# led_driver_3A_flat.net
KiCad netlist of a schematic drawn in EAGLE
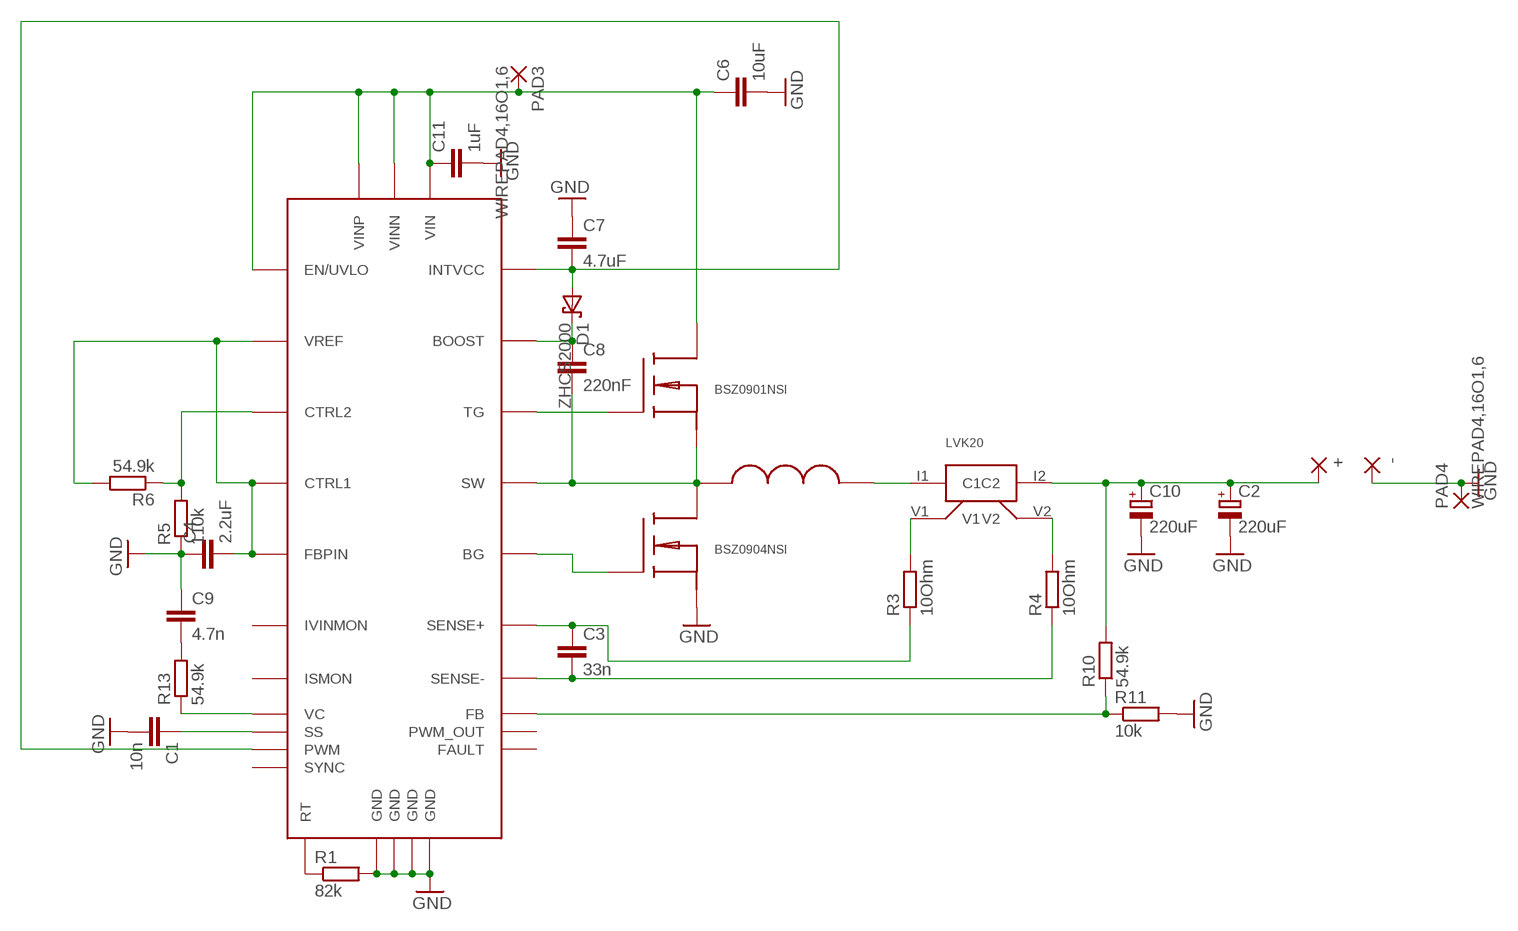
[diagram p0: schematic, sheet 1]

(export (version "E")
  (design (tool "Eeschema 10.0.6"))
  (components
    (comp (ref "+")
      (value "2,15/1,0")
      (footprint "eagle-import:2,15_1,0")
      (libsource (lib "eagle-import") (part "2,15/1,0"))
    )
    (comp (ref "-")
      (value "2,15/1,0")
      (footprint "eagle-import:2,15_1,0")
      (libsource (lib "eagle-import") (part "2,15/1,0"))
    )
    (comp (ref "C1")
      (value "10n")
      (footprint "eagle-import:C0402")
      (libsource (lib "eagle-import") (part "C-EUC0402"))
    )
    (comp (ref "C2")
      (value "220uF")
      (footprint "eagle-import:SMC_D")
      (libsource (lib "eagle-import") (part "CPOL-EUSMCD"))
    )
    (comp (ref "C3")
      (value "33n")
      (footprint "eagle-import:C0402")
      (libsource (lib "eagle-import") (part "C-EUC0402"))
    )
    (comp (ref "C4")
      (value "2.2uF")
      (footprint "eagle-import:C0805")
      (libsource (lib "eagle-import") (part "C-EUC0805"))
    )
    (comp (ref "C6")
      (value "10uF")
      (footprint "eagle-import:C2220K")
      (libsource (lib "eagle-import") (part "C-EUC2220K"))
    )
    (comp (ref "C7")
      (value "4.7uF")
      (footprint "eagle-import:C1206")
      (libsource (lib "eagle-import") (part "C-EUC1206"))
    )
    (comp (ref "C8")
      (value "220nF")
      (footprint "eagle-import:C0603")
      (libsource (lib "eagle-import") (part "C-EUC0603"))
    )
    (comp (ref "C9")
      (value "4.7n")
      (footprint "eagle-import:C0402")
      (libsource (lib "eagle-import") (part "C-EUC0402"))
    )
    (comp (ref "C10")
      (value "220uF")
      (footprint "eagle-import:SMC_D")
      (libsource (lib "eagle-import") (part "CPOL-EUSMCD"))
    )
    (comp (ref "C11")
      (value "1uF")
      (footprint "eagle-import:C1206")
      (libsource (lib "eagle-import") (part "C-EUC1206"))
    )
    (comp (ref "D1")
      (value "ZHCS2000")
      (footprint "eagle-import:SOT23-6")
      (libsource (lib "eagle-import") (part "ZHCS2000"))
    )
    (comp (ref "PAD3")
      (value "WIREPAD4,16O1,6")
      (footprint "eagle-import:4,16O1,6")
      (libsource (lib "eagle-import") (part "WIREPAD4,16O1,6"))
    )
    (comp (ref "PAD4")
      (value "WIREPAD4,16O1,6")
      (footprint "eagle-import:4,16O1,6")
      (libsource (lib "eagle-import") (part "WIREPAD4,16O1,6"))
    )
    (comp (ref "R1")
      (value "82k")
      (footprint "eagle-import:R0402")
      (libsource (lib "eagle-import") (part "R-EU_R0402"))
    )
    (comp (ref "R3")
      (value "10Ohm")
      (footprint "eagle-import:R0402")
      (libsource (lib "eagle-import") (part "R-EU_R0402"))
    )
    (comp (ref "R4")
      (value "10Ohm")
      (footprint "eagle-import:R0402")
      (libsource (lib "eagle-import") (part "R-EU_R0402"))
    )
    (comp (ref "R5")
      (value "110k")
      (footprint "eagle-import:R0402")
      (libsource (lib "eagle-import") (part "R-EU_R0402"))
    )
    (comp (ref "R6")
      (value "54.9k")
      (footprint "eagle-import:R0402")
      (libsource (lib "eagle-import") (part "R-EU_R0402"))
    )
    (comp (ref "R10")
      (value "54.9k")
      (footprint "eagle-import:R0402")
      (libsource (lib "eagle-import") (part "R-EU_R0402"))
    )
    (comp (ref "R11")
      (value "10k")
      (footprint "eagle-import:R0402")
      (libsource (lib "eagle-import") (part "R-EU_R0402"))
    )
    (comp (ref "R13")
      (value "54.9k")
      (footprint "eagle-import:R0402")
      (libsource (lib "eagle-import") (part "R-EU_R0402"))
    )
    (comp (ref "U$1")
      (value "LT3763")
      (footprint "eagle-import:TSSOP-28")
      (libsource (lib "eagle-import") (part "LT3763"))
    )
    (comp (ref "U$2")
      (value "PG0077")
      (footprint "eagle-import:PG0077")
      (libsource (lib "eagle-import") (part "PG0077"))
    )
    (comp (ref "U$3")
      (value "BSZ0901NSI")
      (footprint "eagle-import:BSZ090X")
      (libsource (lib "eagle-import") (part "BSZ090X"))
    )
    (comp (ref "U$4")
      (value "BSZ0904NSI")
      (footprint "eagle-import:BSZ090X")
      (libsource (lib "eagle-import") (part "BSZ090X"))
    )
    (comp (ref "U$5")
      (value "LVK20")
      (footprint "eagle-import:LVK20")
      (libsource (lib "eagle-import") (part "LVK20"))
    )
  )
  (nets
    (net (code "1") (name "GND") (class "Default")
      (node (ref "-") (pin "1") (pinfunction "P_1") (pintype "passive"))
      (node (ref "C1") (pin "2") (pinfunction "2_2") (pintype "passive"))
      (node (ref "C10") (pin "-") (pinfunction "-_-") (pintype "passive"))
      (node (ref "C11") (pin "2") (pinfunction "2_2") (pintype "passive"))
      (node (ref "C2") (pin "-") (pinfunction "-_-") (pintype "passive"))
      (node (ref "C4") (pin "1") (pinfunction "1_1") (pintype "passive"))
      (node (ref "C6") (pin "2") (pinfunction "2_2") (pintype "passive"))
      (node (ref "C7") (pin "1") (pinfunction "1_1") (pintype "passive"))
      (node (ref "C9") (pin "1") (pinfunction "1_1") (pintype "passive"))
      (node (ref "PAD4") (pin "1") (pinfunction "P_1") (pintype "passive"))
      (node (ref "R1") (pin "2") (pinfunction "2_2") (pintype "passive"))
      (node (ref "R11") (pin "2") (pinfunction "2_2") (pintype "passive"))
      (node (ref "R5") (pin "1") (pinfunction "1_1") (pintype "passive"))
      (node (ref "U$1") (pin "P$12") (pinfunction "GND_P$12") (pintype "bidirectional"))
      (node (ref "U$1") (pin "P$23") (pinfunction "GND_P$23") (pintype "bidirectional"))
      (node (ref "U$1") (pin "P$28") (pinfunction "GND_P$28") (pintype "bidirectional"))
      (node (ref "U$1") (pin "TH") (pinfunction "GND_TH") (pintype "bidirectional"))
      (node (ref "U$4") (pin "S@1") (pinfunction "S_S@1") (pintype "bidirectional"))
      (node (ref "U$4") (pin "S@2") (pinfunction "S_S@2") (pintype "bidirectional"))
      (node (ref "U$4") (pin "S@3") (pinfunction "S_S@3") (pintype "bidirectional"))
      (node (ref "U$4") (pin "S@4") (pinfunction "S_S@4") (pintype "bidirectional"))
    )
    (net (code "2") (name "Net-(+-P)") (class "Default")
      (node (ref "+") (pin "1") (pinfunction "P_1") (pintype "passive"))
      (node (ref "C10") (pin "+") (pinfunction "+_+") (pintype "passive"))
      (node (ref "C2") (pin "+") (pinfunction "+_+") (pintype "passive"))
      (node (ref "R10") (pin "2") (pinfunction "2_2") (pintype "passive"))
      (node (ref "U$5") (pin "I2") (pinfunction "C2_I2") (pintype "bidirectional"))
    )
    (net (code "3") (name "Net-(C9-Pad2)") (class "Default")
      (node (ref "C9") (pin "2") (pinfunction "2_2") (pintype "passive"))
      (node (ref "R13") (pin "2") (pinfunction "2_2") (pintype "passive"))
    )
    (net (code "4") (name "Net-(PAD3-P)") (class "Default")
      (node (ref "C11") (pin "1") (pinfunction "1_1") (pintype "passive"))
      (node (ref "C6") (pin "1") (pinfunction "1_1") (pintype "passive"))
      (node (ref "PAD3") (pin "1") (pinfunction "P_1") (pintype "passive"))
      (node (ref "U$1") (pin "P$3") (pinfunction "VIN_P$3") (pintype "bidirectional"))
      (node (ref "U$1") (pin "P$4") (pinfunction "EN/UVLO_P$4") (pintype "bidirectional"))
      (node (ref "U$1") (pin "P$6") (pinfunction "VINN_P$6") (pintype "bidirectional"))
      (node (ref "U$1") (pin "P$7") (pinfunction "VINP_P$7") (pintype "bidirectional"))
      (node (ref "U$3") (pin "D") (pinfunction "D_D") (pintype "bidirectional"))
      (node (ref "U$3") (pin "D@1") (pinfunction "D_D@1") (pintype "bidirectional"))
      (node (ref "U$3") (pin "D@2") (pinfunction "D_D@2") (pintype "bidirectional"))
      (node (ref "U$3") (pin "D@3") (pinfunction "D_D@3") (pintype "bidirectional"))
      (node (ref "U$3") (pin "D@4") (pinfunction "D_D@4") (pintype "bidirectional"))
    )
    (net (code "5") (name "Net-(R3-Pad2)") (class "Default")
      (node (ref "R3") (pin "2") (pinfunction "2_2") (pintype "passive"))
      (node (ref "U$5") (pin "V1") (pinfunction "V1_V1") (pintype "bidirectional"))
    )
    (net (code "6") (name "Net-(R4-Pad2)") (class "Default")
      (node (ref "R4") (pin "2") (pinfunction "2_2") (pintype "passive"))
      (node (ref "U$5") (pin "V2") (pinfunction "V2_V2") (pintype "bidirectional"))
    )
    (net (code "7") (name "Net-(U$1-BG)") (class "Default")
      (node (ref "U$1") (pin "P$1") (pinfunction "BG_P$1") (pintype "bidirectional"))
      (node (ref "U$4") (pin "G") (pinfunction "G_G") (pintype "bidirectional"))
    )
    (net (code "8") (name "Net-(U$1-BOOST)") (class "Default")
      (node (ref "C8") (pin "1") (pinfunction "1_1") (pintype "passive"))
      (node (ref "D1") (pin "1") (pinfunction "K_1") (pintype "passive"))
      (node (ref "D1") (pin "2") (pinfunction "K_2") (pintype "passive"))
      (node (ref "D1") (pin "5") (pinfunction "K_5") (pintype "passive"))
      (node (ref "D1") (pin "6") (pinfunction "K_6") (pintype "passive"))
      (node (ref "U$1") (pin "P$27") (pinfunction "BOOST_P$27") (pintype "bidirectional"))
    )
    (net (code "9") (name "Net-(U$1-CTRL1)") (class "Default")
      (node (ref "C4") (pin "2") (pinfunction "2_2") (pintype "passive"))
      (node (ref "R6") (pin "2") (pinfunction "2_2") (pintype "passive"))
      (node (ref "U$1") (pin "P$10") (pinfunction "FBPIN_P$10") (pintype "bidirectional"))
      (node (ref "U$1") (pin "P$14") (pinfunction "CTRL1_P$14") (pintype "bidirectional"))
      (node (ref "U$1") (pin "P$5") (pinfunction "VREF_P$5") (pintype "bidirectional"))
    )
    (net (code "10") (name "Net-(U$1-CTRL2)") (class "Default")
      (node (ref "R5") (pin "2") (pinfunction "2_2") (pintype "passive"))
      (node (ref "R6") (pin "1") (pinfunction "1_1") (pintype "passive"))
      (node (ref "U$1") (pin "P$13") (pinfunction "CTRL2_P$13") (pintype "bidirectional"))
    )
    (net (code "11") (name "Net-(U$1-FB)") (class "Default")
      (node (ref "R10") (pin "1") (pinfunction "1_1") (pintype "passive"))
      (node (ref "R11") (pin "1") (pinfunction "1_1") (pintype "passive"))
      (node (ref "U$1") (pin "P$11") (pinfunction "FB_P$11") (pintype "bidirectional"))
    )
    (net (code "12") (name "Net-(U$1-INTVCC)") (class "Default")
      (node (ref "C7") (pin "2") (pinfunction "2_2") (pintype "passive"))
      (node (ref "D1") (pin "3") (pinfunction "A_3") (pintype "passive"))
      (node (ref "D1") (pin "4") (pinfunction "A_4") (pintype "passive"))
      (node (ref "U$1") (pin "P$2") (pinfunction "INTVCC_P$2") (pintype "bidirectional"))
      (node (ref "U$1") (pin "P$22") (pinfunction "PWM_P$22") (pintype "bidirectional"))
    )
    (net (code "13") (name "Net-(U$1-RT)") (class "Default")
      (node (ref "R1") (pin "1") (pinfunction "1_1") (pintype "passive"))
      (node (ref "U$1") (pin "P$20") (pinfunction "RT_P$20") (pintype "bidirectional"))
    )
    (net (code "14") (name "Net-(U$1-SENSE+)") (class "Default")
      (node (ref "C3") (pin "1") (pinfunction "1_1") (pintype "passive"))
      (node (ref "R3") (pin "1") (pinfunction "1_1") (pintype "passive"))
      (node (ref "U$1") (pin "P$17") (pinfunction "SENSE+_P$17") (pintype "bidirectional"))
    )
    (net (code "15") (name "Net-(U$1-SENSE-)") (class "Default")
      (node (ref "C3") (pin "2") (pinfunction "2_2") (pintype "passive"))
      (node (ref "R4") (pin "1") (pinfunction "1_1") (pintype "passive"))
      (node (ref "U$1") (pin "P$16") (pinfunction "SENSE-_P$16") (pintype "bidirectional"))
    )
    (net (code "16") (name "Net-(U$1-SS)") (class "Default")
      (node (ref "C1") (pin "1") (pinfunction "1_1") (pintype "passive"))
      (node (ref "U$1") (pin "P$15") (pinfunction "SS_P$15") (pintype "bidirectional"))
    )
    (net (code "17") (name "Net-(U$1-SW)") (class "Default")
      (node (ref "C8") (pin "2") (pinfunction "2_2") (pintype "passive"))
      (node (ref "U$1") (pin "P$26") (pinfunction "SW_P$26") (pintype "bidirectional"))
      (node (ref "U$2") (pin "P$1") (pinfunction "P$1_P$1") (pintype "bidirectional"))
      (node (ref "U$3") (pin "S@1") (pinfunction "S_S@1") (pintype "bidirectional"))
      (node (ref "U$3") (pin "S@2") (pinfunction "S_S@2") (pintype "bidirectional"))
      (node (ref "U$3") (pin "S@3") (pinfunction "S_S@3") (pintype "bidirectional"))
      (node (ref "U$3") (pin "S@4") (pinfunction "S_S@4") (pintype "bidirectional"))
      (node (ref "U$4") (pin "D") (pinfunction "D_D") (pintype "bidirectional"))
      (node (ref "U$4") (pin "D@1") (pinfunction "D_D@1") (pintype "bidirectional"))
      (node (ref "U$4") (pin "D@2") (pinfunction "D_D@2") (pintype "bidirectional"))
      (node (ref "U$4") (pin "D@3") (pinfunction "D_D@3") (pintype "bidirectional"))
      (node (ref "U$4") (pin "D@4") (pinfunction "D_D@4") (pintype "bidirectional"))
    )
    (net (code "18") (name "Net-(U$1-TG)") (class "Default")
      (node (ref "U$1") (pin "P$25") (pinfunction "TG_P$25") (pintype "bidirectional"))
      (node (ref "U$3") (pin "G") (pinfunction "G_G") (pintype "bidirectional"))
    )
    (net (code "19") (name "Net-(U$1-VC)") (class "Default")
      (node (ref "R13") (pin "1") (pinfunction "1_1") (pintype "passive"))
      (node (ref "U$1") (pin "P$18") (pinfunction "VC_P$18") (pintype "bidirectional"))
    )
    (net (code "20") (name "Net-(U$5-C1)") (class "Default")
      (node (ref "U$2") (pin "P$2") (pinfunction "P$2_P$2") (pintype "bidirectional"))
      (node (ref "U$5") (pin "I1") (pinfunction "C1_I1") (pintype "bidirectional"))
    )
    (net (code "21") (name "unconnected-(U$1-FAULT-PadP$9)") (class "Default")
      (node (ref "U$1") (pin "P$9") (pinfunction "FAULT_P$9") (pintype "bidirectional"))
    )
    (net (code "22") (name "unconnected-(U$1-ISMON-PadP$19)") (class "Default")
      (node (ref "U$1") (pin "P$19") (pinfunction "ISMON_P$19") (pintype "bidirectional"))
    )
    (net (code "23") (name "unconnected-(U$1-IVINMON-PadP$8)") (class "Default")
      (node (ref "U$1") (pin "P$8") (pinfunction "IVINMON_P$8") (pintype "bidirectional"))
    )
    (net (code "24") (name "unconnected-(U$1-PWM_OUT-PadP$24)") (class "Default")
      (node (ref "U$1") (pin "P$24") (pinfunction "PWM_OUT_P$24") (pintype "bidirectional"))
    )
    (net (code "25") (name "unconnected-(U$1-SYNC-PadP$21)") (class "Default")
      (node (ref "U$1") (pin "P$21") (pinfunction "SYNC_P$21") (pintype "bidirectional"))
    )
  )
)
